# AmbaSat-03-BME680.net
KiCad netlist of a schematic drawn in EAGLE
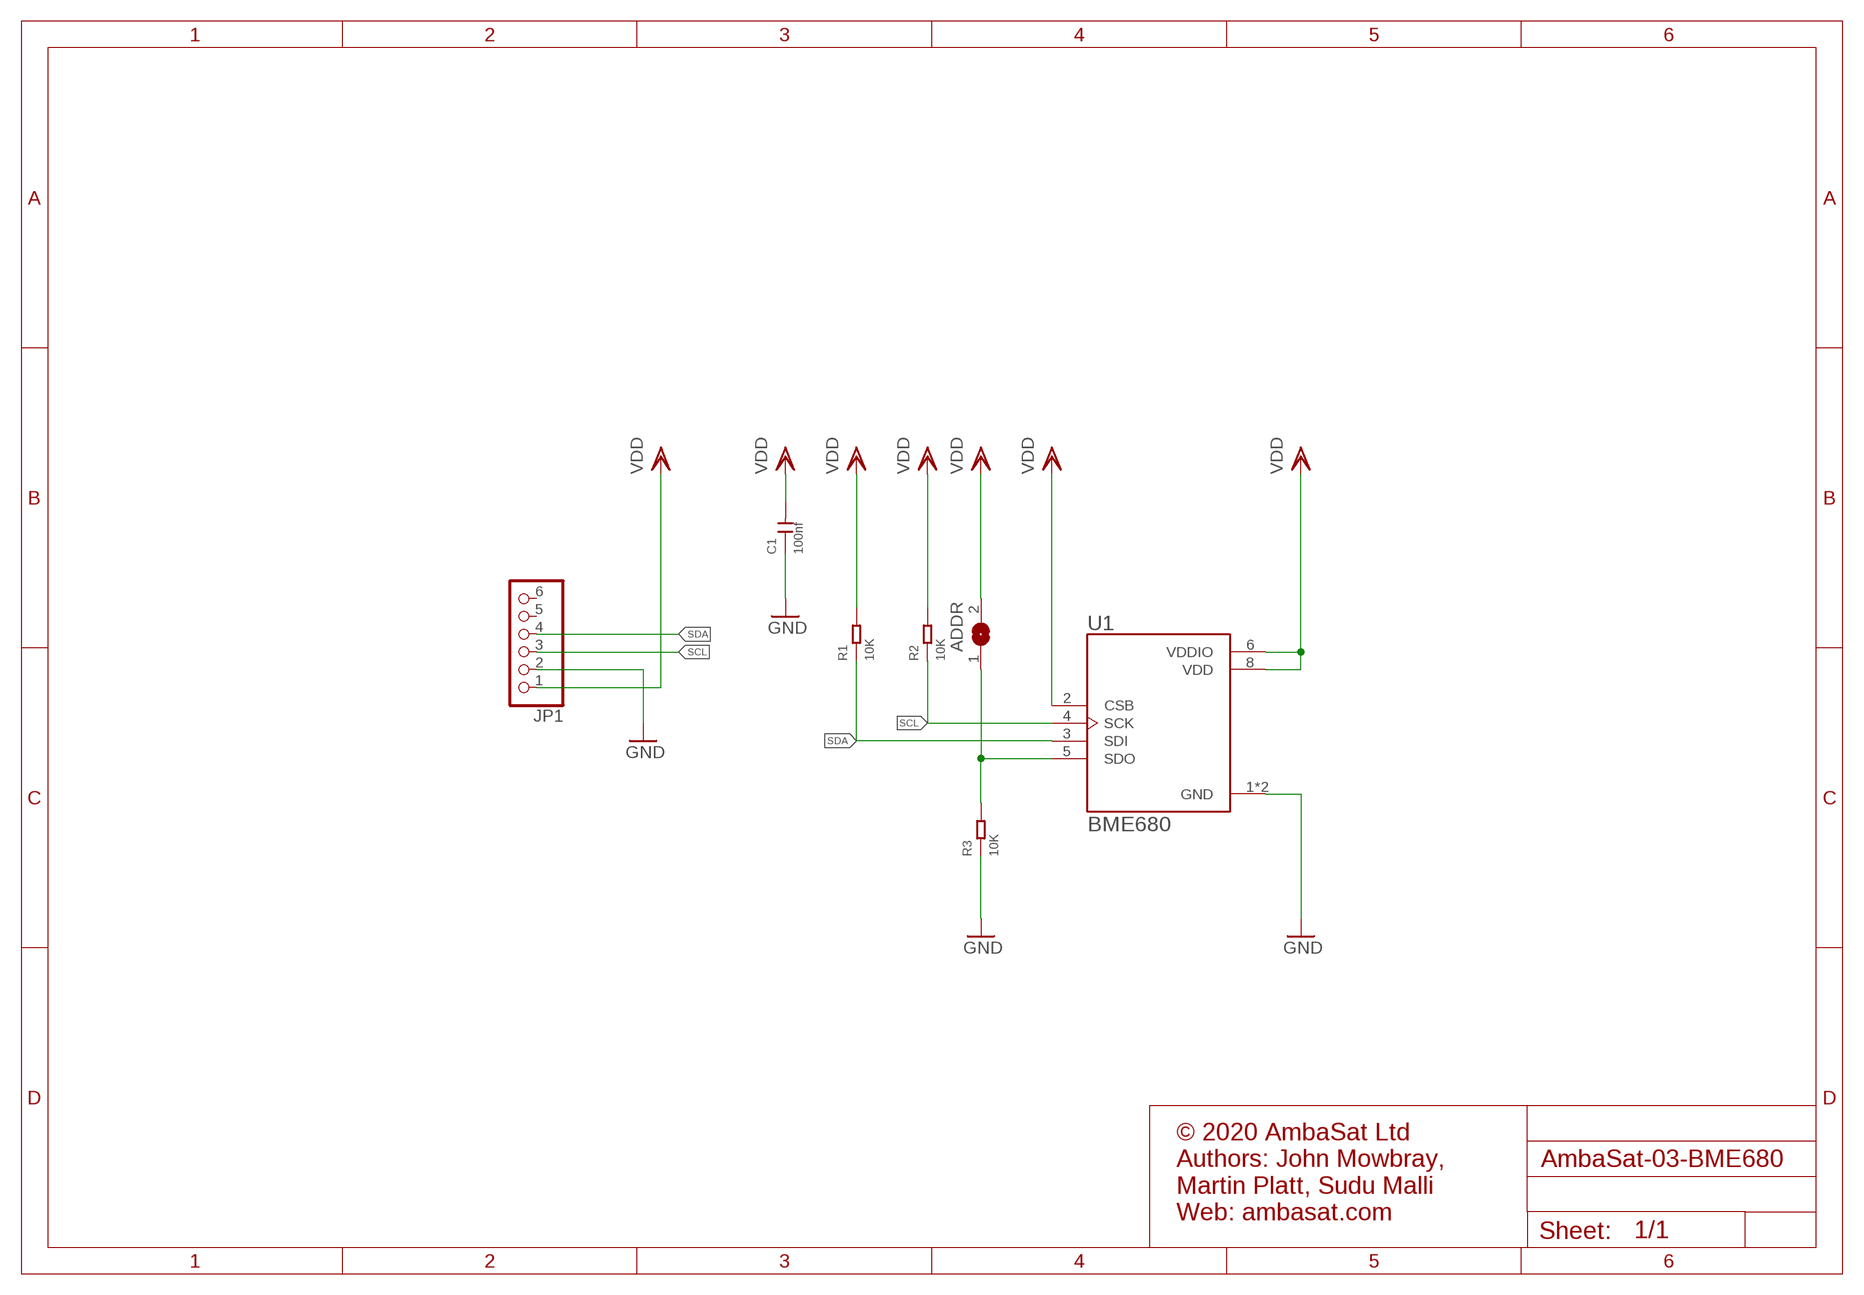
[diagram p0: schematic, sheet 1]

(export (version "E")
  (design (tool "Eeschema 10.0.6"))
  (components
    (comp (ref "ADDR")
      (value "SJ")
      (footprint "eagle-import:SJ")
      (libsource (lib "eagle-import") (part "SJ"))
    )
    (comp (ref "C1")
      (value "100nf")
      (footprint "eagle-import:C0805")
      (fields (field (name "MPN") "CC0805KRX7R9BB104"))
      (libsource (lib "eagle-import") (part "CERAMIC-100NF-50V-10%-X7R(0805)"))
    )
    (comp (ref "JP1")
      (value "HEADER-1X6")
      (footprint "eagle-import:1X06_OVAL")
      (libsource (lib "eagle-import") (part "HEADER-1X6"))
    )
    (comp (ref "R1")
      (value "10K")
      (footprint "eagle-import:R0805")
      (fields (field (name "MPN") "RC0805FR-0710KL"))
      (libsource (lib "eagle-import") (part "SMD-RES-10K-1%-1/8W(0805)"))
    )
    (comp (ref "R2")
      (value "10K")
      (footprint "eagle-import:R0805")
      (fields (field (name "MPN") "RC0805FR-0710KL"))
      (libsource (lib "eagle-import") (part "SMD-RES-10K-1%-1/8W(0805)"))
    )
    (comp (ref "R3")
      (value "10K")
      (footprint "eagle-import:R0805")
      (fields (field (name "MPN") "RC0805FR-0710KL"))
      (libsource (lib "eagle-import") (part "SMD-RES-10K-1%-1/8W(0805)"))
    )
    (comp (ref "U1")
      (value "BME680")
      (footprint "eagle-import:PSON80P300X300X100-8N")
      (fields (field (name "MF") "Bosch Sensortec"))
      (libsource (lib "eagle-import") (part "BME680"))
    )
  )
  (nets
    (net (code "1") (name "GND") (class "Default")
      (node (ref "C1") (pin "1") (pinfunction "1_1") (pintype "passive"))
      (node (ref "JP1") (pin "2") (pinfunction "2_2") (pintype "passive"))
      (node (ref "R3") (pin "1") (pinfunction "1_1") (pintype "passive"))
      (node (ref "U1") (pin "1") (pinfunction "GND_1") (pintype "power_in"))
      (node (ref "U1") (pin "7") (pinfunction "GND_7") (pintype "power_in"))
    )
    (net (code "2") (name "Net-(U1-SDO)") (class "Default")
      (node (ref "ADDR") (pin "1") (pinfunction "1_1") (pintype "passive"))
      (node (ref "R3") (pin "2") (pinfunction "2_2") (pintype "passive"))
      (node (ref "U1") (pin "5") (pinfunction "SDO_5") (pintype "bidirectional"))
    )
    (net (code "3") (name "SCL") (class "Default")
      (node (ref "JP1") (pin "3") (pinfunction "3_3") (pintype "passive"))
      (node (ref "R2") (pin "1") (pinfunction "1_1") (pintype "passive"))
      (node (ref "U1") (pin "4") (pinfunction "SCK_4") (pintype "input"))
    )
    (net (code "4") (name "SDA") (class "Default")
      (node (ref "JP1") (pin "4") (pinfunction "4_4") (pintype "passive"))
      (node (ref "R1") (pin "1") (pinfunction "1_1") (pintype "passive"))
      (node (ref "U1") (pin "3") (pinfunction "SDI_3") (pintype "bidirectional"))
    )
    (net (code "5") (name "VDD") (class "Default")
      (node (ref "ADDR") (pin "2") (pinfunction "2_2") (pintype "passive"))
      (node (ref "C1") (pin "2") (pinfunction "2_2") (pintype "passive"))
      (node (ref "JP1") (pin "1") (pinfunction "1_1") (pintype "passive"))
      (node (ref "R1") (pin "2") (pinfunction "2_2") (pintype "passive"))
      (node (ref "R2") (pin "2") (pinfunction "2_2") (pintype "passive"))
      (node (ref "U1") (pin "2") (pinfunction "CSB_2") (pintype "input"))
      (node (ref "U1") (pin "6") (pinfunction "VDDIO_6") (pintype "power_in"))
      (node (ref "U1") (pin "8") (pinfunction "VDD_8") (pintype "power_in"))
    )
    (net (code "6") (name "unconnected-(JP1-Pad5)") (class "Default")
      (node (ref "JP1") (pin "5") (pinfunction "5_5") (pintype "passive"))
    )
    (net (code "7") (name "unconnected-(JP1-Pad6)") (class "Default")
      (node (ref "JP1") (pin "6") (pinfunction "6_6") (pintype "passive"))
    )
  )
)
